# 05_LMS7002M_Misc.net
KiCad netlist of a schematic drawn in Altium Designer
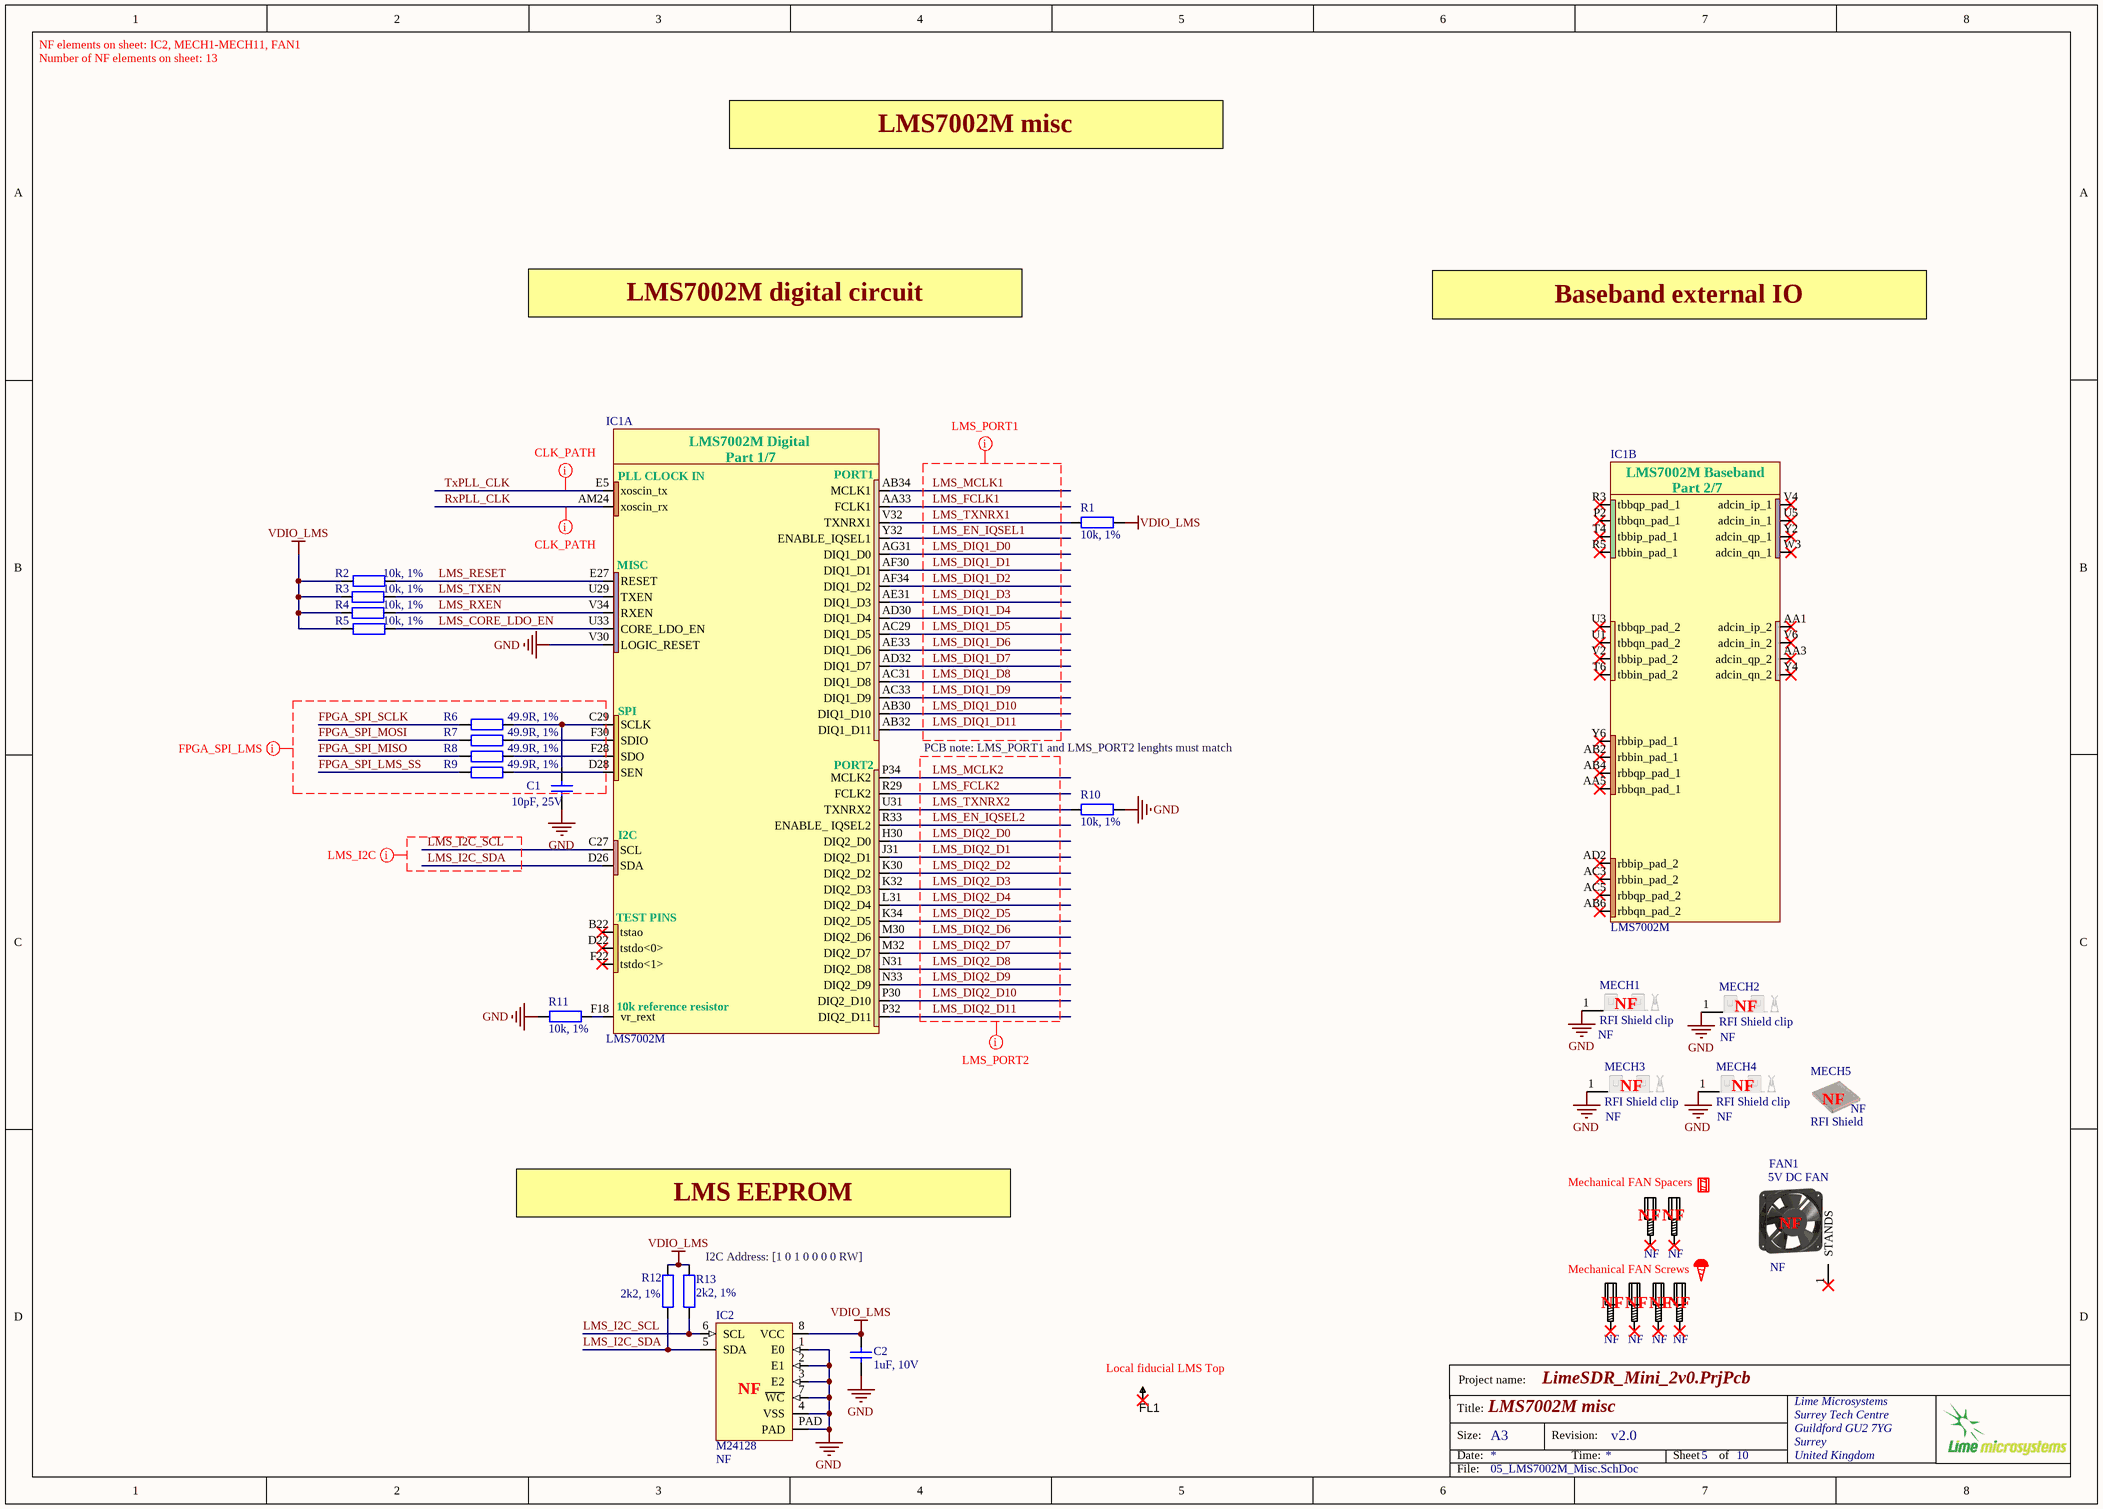
[diagram p0: 05_LMS7002M_Misc.SchDoc]

(export (version "E")
  (design (tool "Eeschema 10.0.6"))
  (components
    (comp (ref "C1")
      (value "10pF, 25V")
      (footprint "CAP0402")
      (fields (field (name "MANUFACTURER") "AVX"))
      (libsource (lib "LimeMicroAltiumLib_schLib") (part "Cap_0402"))
    )
    (comp (ref "C2")
      (value "1uF, 10V")
      (footprint "CAP0402")
      (fields (field (name "MANUFACTURER") "TDK"))
      (libsource (lib "LimeMicroAltiumLib_schLib") (part "Cap_0402"))
    )
    (comp (ref "FAN1")
      (value "5V DC FAN")
      (fields (field (name "MANUFACTURER") "Sunon Fans") (field (name "ASSEMBLY INFO") "NF"))
      (libsource (lib "LimeMicroAltiumLib_schLib") (part "12V_DC_FAN"))
    )
    (comp (ref "FL1")
      (value "Fiducial")
      (footprint "Fiducial_local")
      (libsource (lib "VGTU_Altium_lib") (part "Fiducial"))
    )
    (comp (ref "IC1")
      (value "LMS7002M")
      (footprint "LMS7002M_v5")
      (description "Schematic symbol revision 3. Default footprint - 0.31mm pad")
      (fields (field (name "MANUFACTURER") "Lime Microsystems"))
      (libsource (lib "LimeMicroAltiumLib_schLib") (part "LMS7002Mr3"))
    )
    (comp (ref "IC2")
      (value "M24128")
      (footprint "M24128-DFMC6TG")
      (fields (field (name "MANUFACTURER") "STMicroelectronics") (field (name "ASSEMBLY INFO") "NF"))
      (libsource (lib "LimeMicroAltiumLib_schLib") (part "M24128-DFMC6TG"))
    )
    (comp (ref "MECH1")
      (value "RFI Shield clip")
      (footprint "RFI_SHIELD_CLPS_MINI")
      (fields (field (name "MANUFACTURER") "HARWIN") (field (name "ASSEMBLY INFO") "NF"))
      (libsource (lib "LimeMicroAltiumLib_schLib") (part "RFI_SHIELD_CLIP"))
    )
    (comp (ref "MECH2")
      (value "RFI Shield clip")
      (footprint "RFI_SHIELD_CLPS_MINI")
      (fields (field (name "MANUFACTURER") "HARWIN") (field (name "ASSEMBLY INFO") "NF"))
      (libsource (lib "LimeMicroAltiumLib_schLib") (part "RFI_SHIELD_CLIP"))
    )
    (comp (ref "MECH3")
      (value "RFI Shield clip")
      (footprint "RFI_SHIELD_CLPS_MINI")
      (fields (field (name "MANUFACTURER") "HARWIN") (field (name "ASSEMBLY INFO") "NF"))
      (libsource (lib "LimeMicroAltiumLib_schLib") (part "RFI_SHIELD_CLIP"))
    )
    (comp (ref "MECH4")
      (value "RFI Shield clip")
      (footprint "RFI_SHIELD_CLPS_MINI")
      (fields (field (name "MANUFACTURER") "HARWIN") (field (name "ASSEMBLY INFO") "NF"))
      (libsource (lib "LimeMicroAltiumLib_schLib") (part "RFI_SHIELD_CLIP"))
    )
    (comp (ref "MECH5")
      (value "RFI Shield")
      (footprint "WurthElectronic_RF_shield")
      (fields (field (name "MANUFACTURER") "WURTH ELEKTRONIK") (field (name "ASSEMBLY INFO") "NF"))
      (libsource (lib "LimeMicroAltiumLib_schLib") (part "RFI_SHIELD_1"))
    )
    (comp (ref "MECH6")
      (value "Spacer M3")
      (description "STANDOFF M/F MET 5MM HEX 10MM L")
      (fields (field (name "MANUFACTURER") "BOSSARD") (field (name "ASSEMBLY INFO") "NF"))
      (libsource (lib "LimeMicroAltiumLib_schLib") (part "STANDOFF_M-F_THREADED_M3x8x10mm_HEX_5mm dia"))
    )
    (comp (ref "MECH7")
      (value "Spacer M3")
      (description "STANDOFF M/F MET 5MM HEX 10MM L")
      (fields (field (name "MANUFACTURER") "BOSSARD") (field (name "ASSEMBLY INFO") "NF"))
      (libsource (lib "LimeMicroAltiumLib_schLib") (part "STANDOFF_M-F_THREADED_M3x8x10mm_HEX_5mm dia"))
    )
    (comp (ref "MECH8")
      (value "Screws M3 v1")
      (description "STANDOFF M/F MET 5MM HEX 10MM L")
      (fields (field (name "MANUFACTURER") "KRAFTBERG") (field (name "ASSEMBLY INFO") "NF"))
      (libsource (lib "LimeMicroAltiumLib_schLib") (part "STANDOFF_M-F_THREADED_M3x8x10mm_HEX_5mm dia"))
    )
    (comp (ref "MECH9")
      (value "Screws M3 v1")
      (description "STANDOFF M/F MET 5MM HEX 10MM L")
      (fields (field (name "MANUFACTURER") "KRAFTBERG") (field (name "ASSEMBLY INFO") "NF"))
      (libsource (lib "LimeMicroAltiumLib_schLib") (part "STANDOFF_M-F_THREADED_M3x8x10mm_HEX_5mm dia"))
    )
    (comp (ref "MECH10")
      (value "Screws M3 v2")
      (description "STANDOFF M/F MET 5MM HEX 10MM L")
      (fields (field (name "MANUFACTURER") "KRAFTBERG") (field (name "ASSEMBLY INFO") "NF"))
      (libsource (lib "LimeMicroAltiumLib_schLib") (part "STANDOFF_M-F_THREADED_M3x8x10mm_HEX_5mm dia"))
    )
    (comp (ref "MECH11")
      (value "Screws M3 v2")
      (description "STANDOFF M/F MET 5MM HEX 10MM L")
      (fields (field (name "MANUFACTURER") "KRAFTBERG") (field (name "ASSEMBLY INFO") "NF"))
      (libsource (lib "LimeMicroAltiumLib_schLib") (part "STANDOFF_M-F_THREADED_M3x8x10mm_HEX_5mm dia"))
    )
    (comp (ref "R1")
      (value "10k, 1%")
      (footprint "RES0402")
      (fields (field (name "MANUFACTURER") "Yageo") (field (name "TOLERANCE") "±1%"))
      (libsource (lib "LimeMicroAltiumLib_schLib") (part "Res_0402"))
    )
    (comp (ref "R2")
      (value "10k, 1%")
      (footprint "RES0402")
      (fields (field (name "MANUFACTURER") "Yageo") (field (name "TOLERANCE") "±1%"))
      (libsource (lib "LimeMicroAltiumLib_schLib") (part "Res_0402"))
    )
    (comp (ref "R3")
      (value "10k, 1%")
      (footprint "RES0402")
      (fields (field (name "MANUFACTURER") "Yageo") (field (name "TOLERANCE") "±1%"))
      (libsource (lib "LimeMicroAltiumLib_schLib") (part "Res_0402"))
    )
    (comp (ref "R4")
      (value "10k, 1%")
      (footprint "RES0402")
      (fields (field (name "MANUFACTURER") "Yageo") (field (name "TOLERANCE") "±1%"))
      (libsource (lib "LimeMicroAltiumLib_schLib") (part "Res_0402"))
    )
    (comp (ref "R5")
      (value "10k, 1%")
      (footprint "RES0402")
      (fields (field (name "MANUFACTURER") "Yageo") (field (name "TOLERANCE") "±1%"))
      (libsource (lib "LimeMicroAltiumLib_schLib") (part "Res_0402"))
    )
    (comp (ref "R6")
      (value "49.9R, 1%")
      (footprint "RES0402")
      (fields
        (field (name "TOLERANCE") "±1%")
        (field (name "MANUFACTURER") "Samsung Electro-Mechanics America, Inc.")
      )
      (libsource (lib "LimeMicroAltiumLib_schLib") (part "Res_0402"))
    )
    (comp (ref "R7")
      (value "49.9R, 1%")
      (footprint "RES0402")
      (fields
        (field (name "TOLERANCE") "±1%")
        (field (name "MANUFACTURER") "Samsung Electro-Mechanics America, Inc.")
      )
      (libsource (lib "LimeMicroAltiumLib_schLib") (part "Res_0402"))
    )
    (comp (ref "R8")
      (value "49.9R, 1%")
      (footprint "RES0402")
      (fields
        (field (name "TOLERANCE") "±1%")
        (field (name "MANUFACTURER") "Samsung Electro-Mechanics America, Inc.")
      )
      (libsource (lib "LimeMicroAltiumLib_schLib") (part "Res_0402"))
    )
    (comp (ref "R9")
      (value "49.9R, 1%")
      (footprint "RES0402")
      (fields
        (field (name "TOLERANCE") "±1%")
        (field (name "MANUFACTURER") "Samsung Electro-Mechanics America, Inc.")
      )
      (libsource (lib "LimeMicroAltiumLib_schLib") (part "Res_0402"))
    )
    (comp (ref "R10")
      (value "10k, 1%")
      (footprint "RES0402")
      (fields (field (name "MANUFACTURER") "Yageo") (field (name "TOLERANCE") "±1%"))
      (libsource (lib "LimeMicroAltiumLib_schLib") (part "Res_0402"))
    )
    (comp (ref "R11")
      (value "10k, 1%")
      (footprint "RES0402")
      (fields (field (name "MANUFACTURER") "Yageo") (field (name "TOLERANCE") "±1%"))
      (libsource (lib "LimeMicroAltiumLib_schLib") (part "Res_0402"))
    )
    (comp (ref "R12")
      (value "2k2, 1%")
      (footprint "RES0402")
      (fields (field (name "MANUFACTURER") "Stackpole Electronics Inc") (field (name "TOLERANCE") "±1%"))
      (libsource (lib "LimeMicroAltiumLib_schLib") (part "Res_0402"))
    )
    (comp (ref "R13")
      (value "2k2, 1%")
      (footprint "RES0402")
      (fields (field (name "MANUFACTURER") "Stackpole Electronics Inc") (field (name "TOLERANCE") "±1%"))
      (libsource (lib "LimeMicroAltiumLib_schLib") (part "Res_0402"))
    )
  )
  (nets
    (net (code "1") (name "/FPGA_SPI_LMS_SS") (class "Default")
      (node (ref "R9") (pin "2") (pinfunction "2_2") (pintype "passive"))
    )
    (net (code "2") (name "/FPGA_SPI_MISO") (class "Default")
      (node (ref "R8") (pin "2") (pinfunction "2_2") (pintype "passive"))
    )
    (net (code "3") (name "/FPGA_SPI_MOSI") (class "Default")
      (node (ref "R7") (pin "2") (pinfunction "2_2") (pintype "passive"))
    )
    (net (code "4") (name "/FPGA_SPI_SCLK") (class "Default")
      (node (ref "R6") (pin "2") (pinfunction "2_2") (pintype "passive"))
    )
    (net (code "5") (name "/LMS_CORE_LDO_EN") (class "Default")
      (node (ref "IC1") (pin "U33") (pinfunction "CORE_LDO_EN_U33") (pintype "passive"))
      (node (ref "R5") (pin "1") (pinfunction "1_1") (pintype "passive"))
    )
    (net (code "6") (name "/LMS_DIQ1_D0") (class "Default")
      (node (ref "IC1") (pin "AG31") (pinfunction "DIQ1_D0_AG31") (pintype "passive"))
    )
    (net (code "7") (name "/LMS_DIQ1_D1") (class "Default")
      (node (ref "IC1") (pin "AF30") (pinfunction "DIQ1_D1_AF30") (pintype "passive"))
    )
    (net (code "8") (name "/LMS_DIQ1_D2") (class "Default")
      (node (ref "IC1") (pin "AF34") (pinfunction "DIQ1_D2_AF34") (pintype "passive"))
    )
    (net (code "9") (name "/LMS_DIQ1_D3") (class "Default")
      (node (ref "IC1") (pin "AE31") (pinfunction "DIQ1_D3_AE31") (pintype "passive"))
    )
    (net (code "10") (name "/LMS_DIQ1_D4") (class "Default")
      (node (ref "IC1") (pin "AD30") (pinfunction "DIQ1_D4_AD30") (pintype "passive"))
    )
    (net (code "11") (name "/LMS_DIQ1_D5") (class "Default")
      (node (ref "IC1") (pin "AC29") (pinfunction "DIQ1_D5_AC29") (pintype "passive"))
    )
    (net (code "12") (name "/LMS_DIQ1_D6") (class "Default")
      (node (ref "IC1") (pin "AE33") (pinfunction "DIQ1_D6_AE33") (pintype "passive"))
    )
    (net (code "13") (name "/LMS_DIQ1_D7") (class "Default")
      (node (ref "IC1") (pin "AD32") (pinfunction "DIQ1_D7_AD32") (pintype "passive"))
    )
    (net (code "14") (name "/LMS_DIQ1_D8") (class "Default")
      (node (ref "IC1") (pin "AC31") (pinfunction "DIQ1_D8_AC31") (pintype "passive"))
    )
    (net (code "15") (name "/LMS_DIQ1_D9") (class "Default")
      (node (ref "IC1") (pin "AC33") (pinfunction "DIQ1_D9_AC33") (pintype "passive"))
    )
    (net (code "16") (name "/LMS_DIQ1_D10") (class "Default")
      (node (ref "IC1") (pin "AB30") (pinfunction "DIQ1_D10_AB30") (pintype "passive"))
    )
    (net (code "17") (name "/LMS_DIQ1_D11") (class "Default")
      (node (ref "IC1") (pin "AB32") (pinfunction "DIQ1_D11_AB32") (pintype "passive"))
    )
    (net (code "18") (name "/LMS_DIQ2_D0") (class "Default")
      (node (ref "IC1") (pin "H30") (pinfunction "DIQ2_D0_H30") (pintype "passive"))
    )
    (net (code "19") (name "/LMS_DIQ2_D1") (class "Default")
      (node (ref "IC1") (pin "J31") (pinfunction "DIQ2_D1_J31") (pintype "passive"))
    )
    (net (code "20") (name "/LMS_DIQ2_D2") (class "Default")
      (node (ref "IC1") (pin "K30") (pinfunction "DIQ2_D2_K30") (pintype "passive"))
    )
    (net (code "21") (name "/LMS_DIQ2_D3") (class "Default")
      (node (ref "IC1") (pin "K32") (pinfunction "DIQ2_D3_K32") (pintype "passive"))
    )
    (net (code "22") (name "/LMS_DIQ2_D4") (class "Default")
      (node (ref "IC1") (pin "L31") (pinfunction "DIQ2_D4_L31") (pintype "passive"))
    )
    (net (code "23") (name "/LMS_DIQ2_D5") (class "Default")
      (node (ref "IC1") (pin "K34") (pinfunction "DIQ2_D5_K34") (pintype "passive"))
    )
    (net (code "24") (name "/LMS_DIQ2_D6") (class "Default")
      (node (ref "IC1") (pin "M30") (pinfunction "DIQ2_D6_M30") (pintype "passive"))
    )
    (net (code "25") (name "/LMS_DIQ2_D7") (class "Default")
      (node (ref "IC1") (pin "M32") (pinfunction "DIQ2_D7_M32") (pintype "passive"))
    )
    (net (code "26") (name "/LMS_DIQ2_D8") (class "Default")
      (node (ref "IC1") (pin "N31") (pinfunction "DIQ2_D8_N31") (pintype "passive"))
    )
    (net (code "27") (name "/LMS_DIQ2_D9") (class "Default")
      (node (ref "IC1") (pin "N33") (pinfunction "DIQ2_D9_N33") (pintype "passive"))
    )
    (net (code "28") (name "/LMS_DIQ2_D10") (class "Default")
      (node (ref "IC1") (pin "P30") (pinfunction "DIQ2_D10_P30") (pintype "passive"))
    )
    (net (code "29") (name "/LMS_DIQ2_D11") (class "Default")
      (node (ref "IC1") (pin "P32") (pinfunction "DIQ2_D11_P32") (pintype "passive"))
    )
    (net (code "30") (name "/LMS_EN_IQSEL1") (class "Default")
      (node (ref "IC1") (pin "Y32") (pinfunction "ENABLE_IQSEL1_Y32") (pintype "passive"))
    )
    (net (code "31") (name "/LMS_EN_IQSEL2") (class "Default")
      (node (ref "IC1") (pin "R33") (pinfunction "ENABLE__IQSEL2_R33") (pintype "passive"))
    )
    (net (code "32") (name "/LMS_FCLK1") (class "Default")
      (node (ref "IC1") (pin "AA33") (pinfunction "FCLK1_AA33") (pintype "passive"))
    )
    (net (code "33") (name "/LMS_FCLK2") (class "Default")
      (node (ref "IC1") (pin "R29") (pinfunction "FCLK2_R29") (pintype "passive"))
    )
    (net (code "34") (name "/LMS_I2C_SCL") (class "Default")
      (node (ref "IC1") (pin "C27") (pinfunction "SCL_C27") (pintype "passive"))
      (node (ref "IC2") (pin "6") (pinfunction "SCL_6") (pintype "input"))
      (node (ref "R13") (pin "2") (pinfunction "2_2") (pintype "passive"))
    )
    (net (code "35") (name "/LMS_I2C_SDA") (class "Default")
      (node (ref "IC1") (pin "D26") (pinfunction "SDA_D26") (pintype "passive"))
      (node (ref "IC2") (pin "5") (pinfunction "SDA_5") (pintype "bidirectional"))
      (node (ref "R12") (pin "2") (pinfunction "2_2") (pintype "passive"))
    )
    (net (code "36") (name "/LMS_MCLK1") (class "Default")
      (node (ref "IC1") (pin "AB34") (pinfunction "MCLK1_AB34") (pintype "passive"))
    )
    (net (code "37") (name "/LMS_MCLK2") (class "Default")
      (node (ref "IC1") (pin "P34") (pinfunction "MCLK2_P34") (pintype "passive"))
    )
    (net (code "38") (name "/LMS_RESET") (class "Default")
      (node (ref "IC1") (pin "E27") (pinfunction "RESET_E27") (pintype "passive"))
      (node (ref "R2") (pin "1") (pinfunction "1_1") (pintype "passive"))
    )
    (net (code "39") (name "/LMS_RXEN") (class "Default")
      (node (ref "IC1") (pin "V34") (pinfunction "RXEN_V34") (pintype "passive"))
      (node (ref "R4") (pin "2") (pinfunction "2_2") (pintype "passive"))
    )
    (net (code "40") (name "/LMS_TXEN") (class "Default")
      (node (ref "IC1") (pin "U29") (pinfunction "TXEN_U29") (pintype "passive"))
      (node (ref "R3") (pin "2") (pinfunction "2_2") (pintype "passive"))
    )
    (net (code "41") (name "/LMS_TXNRX1") (class "Default")
      (node (ref "IC1") (pin "V32") (pinfunction "TXNRX1_V32") (pintype "passive"))
      (node (ref "R1") (pin "1") (pinfunction "1_1") (pintype "passive"))
    )
    (net (code "42") (name "/LMS_TXNRX2") (class "Default")
      (node (ref "IC1") (pin "U31") (pinfunction "TXNRX2_U31") (pintype "passive"))
      (node (ref "R10") (pin "1") (pinfunction "1_1") (pintype "passive"))
    )
    (net (code "43") (name "/RxPLL_CLK") (class "Default")
      (node (ref "IC1") (pin "AM24") (pinfunction "xoscin_rx_AM24") (pintype "passive"))
    )
    (net (code "44") (name "/TxPLL_CLK") (class "Default")
      (node (ref "IC1") (pin "E5") (pinfunction "xoscin_tx_E5") (pintype "passive"))
    )
    (net (code "45") (name "GND") (class "Default")
      (node (ref "C1") (pin "2") (pinfunction "2_2") (pintype "passive"))
      (node (ref "C2") (pin "2") (pinfunction "2_2") (pintype "passive"))
      (node (ref "IC1") (pin "V30") (pinfunction "LOGIC_RESET_V30") (pintype "passive"))
      (node (ref "IC2") (pin "1") (pinfunction "E0_1") (pintype "input"))
      (node (ref "IC2") (pin "2") (pinfunction "E1_2") (pintype "input"))
      (node (ref "IC2") (pin "3") (pinfunction "E2_3") (pintype "input"))
      (node (ref "IC2") (pin "4") (pinfunction "VSS_4") (pintype "power_in"))
      (node (ref "IC2") (pin "7") (pinfunction "~{WC}_7") (pintype "input"))
      (node (ref "IC2") (pin "PAD") (pinfunction "PAD_PAD") (pintype "power_in"))
      (node (ref "MECH1") (pin "1") (pinfunction "GND_1") (pintype "passive"))
      (node (ref "MECH2") (pin "1") (pinfunction "GND_1") (pintype "passive"))
      (node (ref "MECH3") (pin "1") (pinfunction "GND_1") (pintype "passive"))
      (node (ref "MECH4") (pin "1") (pinfunction "GND_1") (pintype "passive"))
      (node (ref "R10") (pin "2") (pinfunction "2_2") (pintype "passive"))
      (node (ref "R11") (pin "2") (pinfunction "2_2") (pintype "passive"))
    )
    (net (code "46") (name "Net-(IC1A-SCLK)") (class "Default")
      (node (ref "C1") (pin "1") (pinfunction "1_1") (pintype "passive"))
      (node (ref "IC1") (pin "C29") (pinfunction "SCLK_C29") (pintype "passive"))
      (node (ref "R6") (pin "1") (pinfunction "1_1") (pintype "passive"))
    )
    (net (code "47") (name "Net-(IC1A-SDIO)") (class "Default")
      (node (ref "IC1") (pin "F30") (pinfunction "SDIO_F30") (pintype "passive"))
      (node (ref "R7") (pin "1") (pinfunction "1_1") (pintype "passive"))
    )
    (net (code "48") (name "Net-(IC1A-SDO)") (class "Default")
      (node (ref "IC1") (pin "F28") (pinfunction "SDO_F28") (pintype "passive"))
      (node (ref "R8") (pin "1") (pinfunction "1_1") (pintype "passive"))
    )
    (net (code "49") (name "Net-(IC1A-SEN)") (class "Default")
      (node (ref "IC1") (pin "D28") (pinfunction "SEN_D28") (pintype "passive"))
      (node (ref "R9") (pin "1") (pinfunction "1_1") (pintype "passive"))
    )
    (net (code "50") (name "Net-(IC1A-vr_rext)") (class "Default")
      (node (ref "IC1") (pin "F18") (pinfunction "vr_rext_F18") (pintype "passive"))
      (node (ref "R11") (pin "1") (pinfunction "1_1") (pintype "passive"))
    )
    (net (code "51") (name "VDIO_LMS") (class "Default")
      (node (ref "C2") (pin "1") (pinfunction "1_1") (pintype "passive"))
      (node (ref "IC2") (pin "8") (pinfunction "VCC_8") (pintype "power_in"))
      (node (ref "R1") (pin "2") (pinfunction "2_2") (pintype "passive"))
      (node (ref "R12") (pin "1") (pinfunction "1_1") (pintype "passive"))
      (node (ref "R13") (pin "1") (pinfunction "1_1") (pintype "passive"))
      (node (ref "R2") (pin "2") (pinfunction "2_2") (pintype "passive"))
      (node (ref "R3") (pin "1") (pinfunction "1_1") (pintype "passive"))
      (node (ref "R4") (pin "1") (pinfunction "1_1") (pintype "passive"))
      (node (ref "R5") (pin "2") (pinfunction "2_2") (pintype "passive"))
    )
    (net (code "52") (name "unconnected-(FAN1-STANDS-Pad1)") (class "Default")
      (node (ref "FAN1") (pin "1") (pinfunction "STANDS_1") (pintype "passive+no_connect"))
    )
    (net (code "53") (name "unconnected-(FL1-Pad1)") (class "Default")
      (node (ref "FL1") (pin "1") (pintype "passive+no_connect"))
    )
    (net (code "54") (name "unconnected-(IC1A-tstao-PadB22)") (class "Default")
      (node (ref "IC1") (pin "B22") (pinfunction "tstao_B22") (pintype "passive+no_connect"))
    )
    (net (code "55") (name "unconnected-(IC1A-tstdo<0>-PadD22)") (class "Default")
      (node (ref "IC1") (pin "D22") (pinfunction "tstdo<0>_D22") (pintype "passive+no_connect"))
    )
    (net (code "56") (name "unconnected-(IC1A-tstdo<1>-PadF22)") (class "Default")
      (node (ref "IC1") (pin "F22") (pinfunction "tstdo<1>_F22") (pintype "passive+no_connect"))
    )
    (net (code "57") (name "unconnected-(IC1B-adcin_in_1-PadU5)") (class "Default")
      (node (ref "IC1") (pin "U5") (pinfunction "adcin_in_1_U5") (pintype "passive+no_connect"))
    )
    (net (code "58") (name "unconnected-(IC1B-adcin_in_2-PadV6)") (class "Default")
      (node (ref "IC1") (pin "V6") (pinfunction "adcin_in_2_V6") (pintype "passive+no_connect"))
    )
    (net (code "59") (name "unconnected-(IC1B-adcin_ip_1-PadV4)") (class "Default")
      (node (ref "IC1") (pin "V4") (pinfunction "adcin_ip_1_V4") (pintype "passive+no_connect"))
    )
    (net (code "60") (name "unconnected-(IC1B-adcin_ip_2-PadAA1)") (class "Default")
      (node (ref "IC1") (pin "AA1") (pinfunction "adcin_ip_2_AA1") (pintype "passive+no_connect"))
    )
    (net (code "61") (name "unconnected-(IC1B-adcin_qn_1-PadW3)") (class "Default")
      (node (ref "IC1") (pin "W3") (pinfunction "adcin_qn_1_W3") (pintype "passive+no_connect"))
    )
    (net (code "62") (name "unconnected-(IC1B-adcin_qn_2-PadY4)") (class "Default")
      (node (ref "IC1") (pin "Y4") (pinfunction "adcin_qn_2_Y4") (pintype "passive+no_connect"))
    )
    (net (code "63") (name "unconnected-(IC1B-adcin_qp_1-PadY2)") (class "Default")
      (node (ref "IC1") (pin "Y2") (pinfunction "adcin_qp_1_Y2") (pintype "passive+no_connect"))
    )
    (net (code "64") (name "unconnected-(IC1B-adcin_qp_2-PadAA3)") (class "Default")
      (node (ref "IC1") (pin "AA3") (pinfunction "adcin_qp_2_AA3") (pintype "passive+no_connect"))
    )
    (net (code "65") (name "unconnected-(IC1B-rbbin_pad_1-PadAB2)") (class "Default")
      (node (ref "IC1") (pin "AB2") (pinfunction "rbbin_pad_1_AB2") (pintype "passive+no_connect"))
    )
    (net (code "66") (name "unconnected-(IC1B-rbbin_pad_2-PadAC3)") (class "Default")
      (node (ref "IC1") (pin "AC3") (pinfunction "rbbin_pad_2_AC3") (pintype "passive+no_connect"))
    )
    (net (code "67") (name "unconnected-(IC1B-rbbip_pad_1-PadY6)") (class "Default")
      (node (ref "IC1") (pin "Y6") (pinfunction "rbbip_pad_1_Y6") (pintype "passive+no_connect"))
    )
    (net (code "68") (name "unconnected-(IC1B-rbbip_pad_2-PadAD2)") (class "Default")
      (node (ref "IC1") (pin "AD2") (pinfunction "rbbip_pad_2_AD2") (pintype "passive+no_connect"))
    )
    (net (code "69") (name "unconnected-(IC1B-rbbqn_pad_1-PadAA5)") (class "Default")
      (node (ref "IC1") (pin "AA5") (pinfunction "rbbqn_pad_1_AA5") (pintype "passive+no_connect"))
    )
    (net (code "70") (name "unconnected-(IC1B-rbbqn_pad_2-PadAB6)") (class "Default")
      (node (ref "IC1") (pin "AB6") (pinfunction "rbbqn_pad_2_AB6") (pintype "passive+no_connect"))
    )
    (net (code "71") (name "unconnected-(IC1B-rbbqp_pad_1-PadAB4)") (class "Default")
      (node (ref "IC1") (pin "AB4") (pinfunction "rbbqp_pad_1_AB4") (pintype "passive+no_connect"))
    )
    (net (code "72") (name "unconnected-(IC1B-rbbqp_pad_2-PadAC5)") (class "Default")
      (node (ref "IC1") (pin "AC5") (pinfunction "rbbqp_pad_2_AC5") (pintype "passive+no_connect"))
    )
    (net (code "73") (name "unconnected-(IC1B-tbbin_pad_1-PadR5)") (class "Default")
      (node (ref "IC1") (pin "R5") (pinfunction "tbbin_pad_1_R5") (pintype "passive+no_connect"))
    )
    (net (code "74") (name "unconnected-(IC1B-tbbin_pad_2-PadT6)") (class "Default")
      (node (ref "IC1") (pin "T6") (pinfunction "tbbin_pad_2_T6") (pintype "passive+no_connect"))
    )
    (net (code "75") (name "unconnected-(IC1B-tbbip_pad_1-PadT4)") (class "Default")
      (node (ref "IC1") (pin "T4") (pinfunction "tbbip_pad_1_T4") (pintype "passive+no_connect"))
    )
    (net (code "76") (name "unconnected-(IC1B-tbbip_pad_2-PadV2)") (class "Default")
      (node (ref "IC1") (pin "V2") (pinfunction "tbbip_pad_2_V2") (pintype "passive+no_connect"))
    )
    (net (code "77") (name "unconnected-(IC1B-tbbqn_pad_1-PadP2)") (class "Default")
      (node (ref "IC1") (pin "P2") (pinfunction "tbbqn_pad_1_P2") (pintype "passive+no_connect"))
    )
    (net (code "78") (name "unconnected-(IC1B-tbbqn_pad_2-PadU1)") (class "Default")
      (node (ref "IC1") (pin "U1") (pinfunction "tbbqn_pad_2_U1") (pintype "passive+no_connect"))
    )
    (net (code "79") (name "unconnected-(IC1B-tbbqp_pad_1-PadR3)") (class "Default")
      (node (ref "IC1") (pin "R3") (pinfunction "tbbqp_pad_1_R3") (pintype "passive+no_connect"))
    )
    (net (code "80") (name "unconnected-(IC1B-tbbqp_pad_2-PadU3)") (class "Default")
      (node (ref "IC1") (pin "U3") (pinfunction "tbbqp_pad_2_U3") (pintype "passive+no_connect"))
    )
    (net (code "81") (name "unconnected-(MECH6-PadMH1)") (class "Default")
      (node (ref "MECH6") (pin "MH1") (pinfunction "MH1_MH1") (pintype "passive+no_connect"))
    )
    (net (code "82") (name "unconnected-(MECH7-PadMH1)") (class "Default")
      (node (ref "MECH7") (pin "MH1") (pinfunction "MH1_MH1") (pintype "passive+no_connect"))
    )
    (net (code "83") (name "unconnected-(MECH8-PadMH1)") (class "Default")
      (node (ref "MECH8") (pin "MH1") (pinfunction "MH1_MH1") (pintype "passive+no_connect"))
    )
    (net (code "84") (name "unconnected-(MECH9-PadMH1)") (class "Default")
      (node (ref "MECH9") (pin "MH1") (pinfunction "MH1_MH1") (pintype "passive+no_connect"))
    )
    (net (code "85") (name "unconnected-(MECH10-PadMH1)") (class "Default")
      (node (ref "MECH10") (pin "MH1") (pinfunction "MH1_MH1") (pintype "passive+no_connect"))
    )
    (net (code "86") (name "unconnected-(MECH11-PadMH1)") (class "Default")
      (node (ref "MECH11") (pin "MH1") (pinfunction "MH1_MH1") (pintype "passive+no_connect"))
    )
  )
)
